# design.net
KiCad netlist of a schematic drawn in EasyEDA
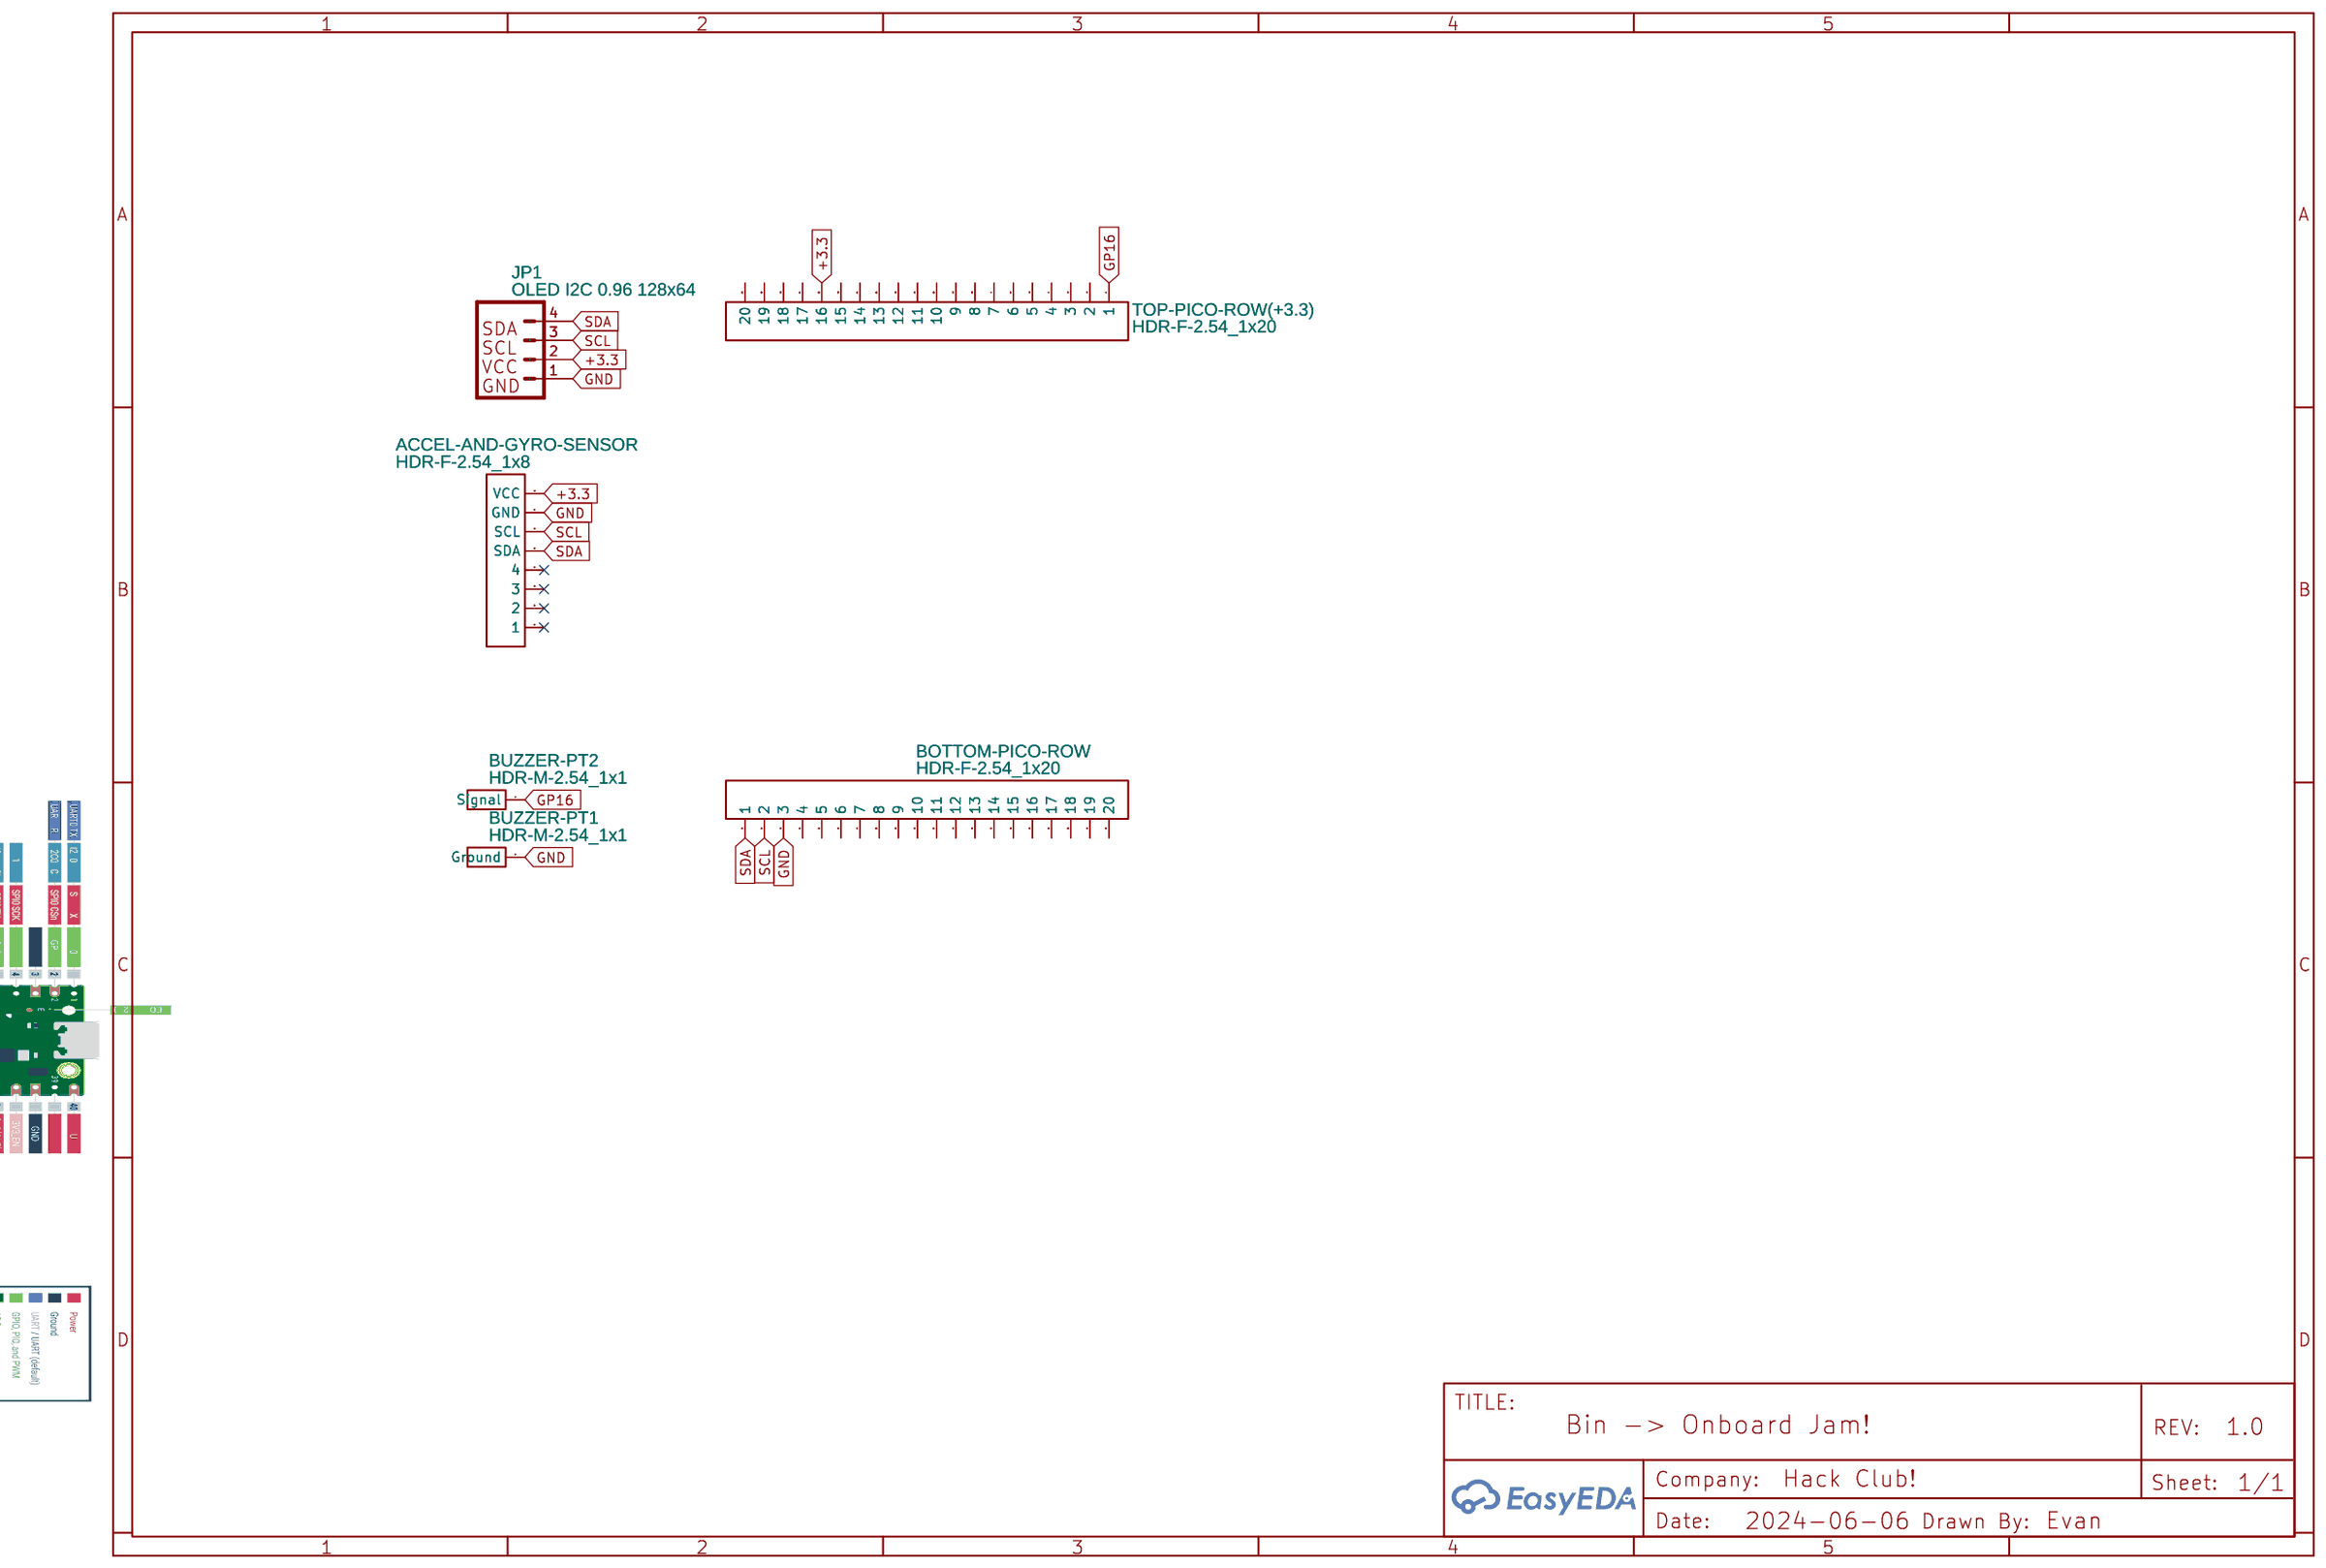
[diagram p0: schematic sheet]

(export (version "E")
  (design (tool "Eeschema 10.0.6"))
  (components
    (comp (ref "ACCEL-AND-GYRO-SENSOR") (value "HDR-F-2.54_1x8") (libsource (lib "") (part "HDR-F-2.54_1x8")))
    (comp (ref "BOTTOM-PICO-ROW") (value "HDR-F-2.54_1x20") (libsource (lib "") (part "HDR-F-2.54_1x20")))
    (comp (ref "BUZZER-PT1") (value "HDR-M-2.54_1x1") (libsource (lib "") (part "HDR-M-2.54_1x1_1")))
    (comp (ref "BUZZER-PT2") (value "HDR-M-2.54_1x1") (libsource (lib "") (part "HDR-M-2.54_1x1")))
    (comp (ref "JP1") (value "OLED I2C 0.96 128x64") (libsource (lib "") (part "OLED I2C 0.96 128x64")))
    (comp (ref "TOP-PICO-ROW(+3.3)")
      (value "HDR-F-2.54_1x20")
      (libsource (lib "") (part "HDR-F-2.54_1x20_1"))
    )
  )
  (nets
    (net (code "1") (name "+3.3") (class "Default")
      (node (ref "ACCEL-AND-GYRO-SENSOR") (pin "8") (pinfunction "VCC_8") (pintype "unspecified"))
      (node (ref "JP1") (pin "2") (pinfunction "2_2") (pintype "unspecified"))
      (node (ref "TOP-PICO-ROW(+3.3)") (pin "16") (pinfunction "16_16") (pintype "unspecified"))
    )
    (net (code "2") (name "GND") (class "Default")
      (node (ref "ACCEL-AND-GYRO-SENSOR") (pin "7") (pinfunction "GND_7") (pintype "unspecified"))
      (node (ref "BOTTOM-PICO-ROW") (pin "3") (pinfunction "3_3") (pintype "unspecified"))
      (node (ref "BUZZER-PT1") (pin "1") (pinfunction "Ground_1") (pintype "input"))
      (node (ref "JP1") (pin "1") (pinfunction "1_1") (pintype "unspecified"))
    )
    (net (code "3") (name "GP16") (class "Default")
      (node (ref "BUZZER-PT2") (pin "1") (pinfunction "Signal_1") (pintype "input"))
      (node (ref "TOP-PICO-ROW(+3.3)") (pin "1") (pinfunction "1_1") (pintype "unspecified"))
    )
    (net (code "4") (name "SCL") (class "Default")
      (node (ref "ACCEL-AND-GYRO-SENSOR") (pin "6") (pinfunction "SCL_6") (pintype "unspecified"))
      (node (ref "BOTTOM-PICO-ROW") (pin "2") (pinfunction "2_2") (pintype "unspecified"))
      (node (ref "JP1") (pin "3") (pinfunction "3_3") (pintype "unspecified"))
    )
    (net (code "5") (name "SDA") (class "Default")
      (node (ref "ACCEL-AND-GYRO-SENSOR") (pin "5") (pinfunction "SDA_5") (pintype "unspecified"))
      (node (ref "BOTTOM-PICO-ROW") (pin "1") (pinfunction "1_1") (pintype "unspecified"))
      (node (ref "JP1") (pin "4") (pinfunction "4_4") (pintype "unspecified"))
    )
    (net (code "6") (name "unconnected-(ACCEL-AND-GYRO-SENSOR-Pad1)") (class "Default")
      (node (ref "ACCEL-AND-GYRO-SENSOR") (pin "1") (pinfunction "1_1") (pintype "unspecified+no_connect"))
    )
    (net (code "7") (name "unconnected-(ACCEL-AND-GYRO-SENSOR-Pad2)") (class "Default")
      (node (ref "ACCEL-AND-GYRO-SENSOR") (pin "2") (pinfunction "2_2") (pintype "unspecified+no_connect"))
    )
    (net (code "8") (name "unconnected-(ACCEL-AND-GYRO-SENSOR-Pad3)") (class "Default")
      (node (ref "ACCEL-AND-GYRO-SENSOR") (pin "3") (pinfunction "3_3") (pintype "unspecified+no_connect"))
    )
    (net (code "9") (name "unconnected-(ACCEL-AND-GYRO-SENSOR-Pad4)") (class "Default")
      (node (ref "ACCEL-AND-GYRO-SENSOR") (pin "4") (pinfunction "4_4") (pintype "unspecified+no_connect"))
    )
    (net (code "10") (name "unconnected-(BOTTOM-PICO-ROW-Pad4)") (class "Default")
      (node (ref "BOTTOM-PICO-ROW") (pin "4") (pinfunction "4_4") (pintype "unspecified"))
    )
    (net (code "11") (name "unconnected-(BOTTOM-PICO-ROW-Pad5)") (class "Default")
      (node (ref "BOTTOM-PICO-ROW") (pin "5") (pinfunction "5_5") (pintype "unspecified"))
    )
    (net (code "12") (name "unconnected-(BOTTOM-PICO-ROW-Pad6)") (class "Default")
      (node (ref "BOTTOM-PICO-ROW") (pin "6") (pinfunction "6_6") (pintype "unspecified"))
    )
    (net (code "13") (name "unconnected-(BOTTOM-PICO-ROW-Pad7)") (class "Default")
      (node (ref "BOTTOM-PICO-ROW") (pin "7") (pinfunction "7_7") (pintype "unspecified"))
    )
    (net (code "14") (name "unconnected-(BOTTOM-PICO-ROW-Pad8)") (class "Default")
      (node (ref "BOTTOM-PICO-ROW") (pin "8") (pinfunction "8_8") (pintype "unspecified"))
    )
    (net (code "15") (name "unconnected-(BOTTOM-PICO-ROW-Pad9)") (class "Default")
      (node (ref "BOTTOM-PICO-ROW") (pin "9") (pinfunction "9_9") (pintype "unspecified"))
    )
    (net (code "16") (name "unconnected-(BOTTOM-PICO-ROW-Pad10)") (class "Default")
      (node (ref "BOTTOM-PICO-ROW") (pin "10") (pinfunction "10_10") (pintype "unspecified"))
    )
    (net (code "17") (name "unconnected-(BOTTOM-PICO-ROW-Pad11)") (class "Default")
      (node (ref "BOTTOM-PICO-ROW") (pin "11") (pinfunction "11_11") (pintype "unspecified"))
    )
    (net (code "18") (name "unconnected-(BOTTOM-PICO-ROW-Pad12)") (class "Default")
      (node (ref "BOTTOM-PICO-ROW") (pin "12") (pinfunction "12_12") (pintype "unspecified"))
    )
    (net (code "19") (name "unconnected-(BOTTOM-PICO-ROW-Pad13)") (class "Default")
      (node (ref "BOTTOM-PICO-ROW") (pin "13") (pinfunction "13_13") (pintype "unspecified"))
    )
    (net (code "20") (name "unconnected-(BOTTOM-PICO-ROW-Pad14)") (class "Default")
      (node (ref "BOTTOM-PICO-ROW") (pin "14") (pinfunction "14_14") (pintype "unspecified"))
    )
    (net (code "21") (name "unconnected-(BOTTOM-PICO-ROW-Pad15)") (class "Default")
      (node (ref "BOTTOM-PICO-ROW") (pin "15") (pinfunction "15_15") (pintype "unspecified"))
    )
    (net (code "22") (name "unconnected-(BOTTOM-PICO-ROW-Pad16)") (class "Default")
      (node (ref "BOTTOM-PICO-ROW") (pin "16") (pinfunction "16_16") (pintype "unspecified"))
    )
    (net (code "23") (name "unconnected-(BOTTOM-PICO-ROW-Pad17)") (class "Default")
      (node (ref "BOTTOM-PICO-ROW") (pin "17") (pinfunction "17_17") (pintype "unspecified"))
    )
    (net (code "24") (name "unconnected-(BOTTOM-PICO-ROW-Pad18)") (class "Default")
      (node (ref "BOTTOM-PICO-ROW") (pin "18") (pinfunction "18_18") (pintype "unspecified"))
    )
    (net (code "25") (name "unconnected-(BOTTOM-PICO-ROW-Pad19)") (class "Default")
      (node (ref "BOTTOM-PICO-ROW") (pin "19") (pinfunction "19_19") (pintype "unspecified"))
    )
    (net (code "26") (name "unconnected-(BOTTOM-PICO-ROW-Pad20)") (class "Default")
      (node (ref "BOTTOM-PICO-ROW") (pin "20") (pinfunction "20_20") (pintype "unspecified"))
    )
    (net (code "27") (name "unconnected-(TOP-PICO-ROW(+3.3)-Pad2)") (class "Default")
      (node (ref "TOP-PICO-ROW(+3.3)") (pin "2") (pinfunction "2_2") (pintype "unspecified"))
    )
    (net (code "28") (name "unconnected-(TOP-PICO-ROW(+3.3)-Pad3)") (class "Default")
      (node (ref "TOP-PICO-ROW(+3.3)") (pin "3") (pinfunction "3_3") (pintype "unspecified"))
    )
    (net (code "29") (name "unconnected-(TOP-PICO-ROW(+3.3)-Pad4)") (class "Default")
      (node (ref "TOP-PICO-ROW(+3.3)") (pin "4") (pinfunction "4_4") (pintype "unspecified"))
    )
    (net (code "30") (name "unconnected-(TOP-PICO-ROW(+3.3)-Pad5)") (class "Default")
      (node (ref "TOP-PICO-ROW(+3.3)") (pin "5") (pinfunction "5_5") (pintype "unspecified"))
    )
    (net (code "31") (name "unconnected-(TOP-PICO-ROW(+3.3)-Pad6)") (class "Default")
      (node (ref "TOP-PICO-ROW(+3.3)") (pin "6") (pinfunction "6_6") (pintype "unspecified"))
    )
    (net (code "32") (name "unconnected-(TOP-PICO-ROW(+3.3)-Pad7)") (class "Default")
      (node (ref "TOP-PICO-ROW(+3.3)") (pin "7") (pinfunction "7_7") (pintype "unspecified"))
    )
    (net (code "33") (name "unconnected-(TOP-PICO-ROW(+3.3)-Pad8)") (class "Default")
      (node (ref "TOP-PICO-ROW(+3.3)") (pin "8") (pinfunction "8_8") (pintype "unspecified"))
    )
    (net (code "34") (name "unconnected-(TOP-PICO-ROW(+3.3)-Pad9)") (class "Default")
      (node (ref "TOP-PICO-ROW(+3.3)") (pin "9") (pinfunction "9_9") (pintype "unspecified"))
    )
    (net (code "35") (name "unconnected-(TOP-PICO-ROW(+3.3)-Pad10)") (class "Default")
      (node (ref "TOP-PICO-ROW(+3.3)") (pin "10") (pinfunction "10_10") (pintype "unspecified"))
    )
    (net (code "36") (name "unconnected-(TOP-PICO-ROW(+3.3)-Pad11)") (class "Default")
      (node (ref "TOP-PICO-ROW(+3.3)") (pin "11") (pinfunction "11_11") (pintype "unspecified"))
    )
    (net (code "37") (name "unconnected-(TOP-PICO-ROW(+3.3)-Pad12)") (class "Default")
      (node (ref "TOP-PICO-ROW(+3.3)") (pin "12") (pinfunction "12_12") (pintype "unspecified"))
    )
    (net (code "38") (name "unconnected-(TOP-PICO-ROW(+3.3)-Pad13)") (class "Default")
      (node (ref "TOP-PICO-ROW(+3.3)") (pin "13") (pinfunction "13_13") (pintype "unspecified"))
    )
    (net (code "39") (name "unconnected-(TOP-PICO-ROW(+3.3)-Pad14)") (class "Default")
      (node (ref "TOP-PICO-ROW(+3.3)") (pin "14") (pinfunction "14_14") (pintype "unspecified"))
    )
    (net (code "40") (name "unconnected-(TOP-PICO-ROW(+3.3)-Pad15)") (class "Default")
      (node (ref "TOP-PICO-ROW(+3.3)") (pin "15") (pinfunction "15_15") (pintype "unspecified"))
    )
    (net (code "41") (name "unconnected-(TOP-PICO-ROW(+3.3)-Pad17)") (class "Default")
      (node (ref "TOP-PICO-ROW(+3.3)") (pin "17") (pinfunction "17_17") (pintype "unspecified"))
    )
    (net (code "42") (name "unconnected-(TOP-PICO-ROW(+3.3)-Pad18)") (class "Default")
      (node (ref "TOP-PICO-ROW(+3.3)") (pin "18") (pinfunction "18_18") (pintype "unspecified"))
    )
    (net (code "43") (name "unconnected-(TOP-PICO-ROW(+3.3)-Pad19)") (class "Default")
      (node (ref "TOP-PICO-ROW(+3.3)") (pin "19") (pinfunction "19_19") (pintype "unspecified"))
    )
    (net (code "44") (name "unconnected-(TOP-PICO-ROW(+3.3)-Pad20)") (class "Default")
      (node (ref "TOP-PICO-ROW(+3.3)") (pin "20") (pinfunction "20_20") (pintype "unspecified"))
    )
  )
)
